# lampe.net
KiCad netlist of a schematic drawn in EAGLE
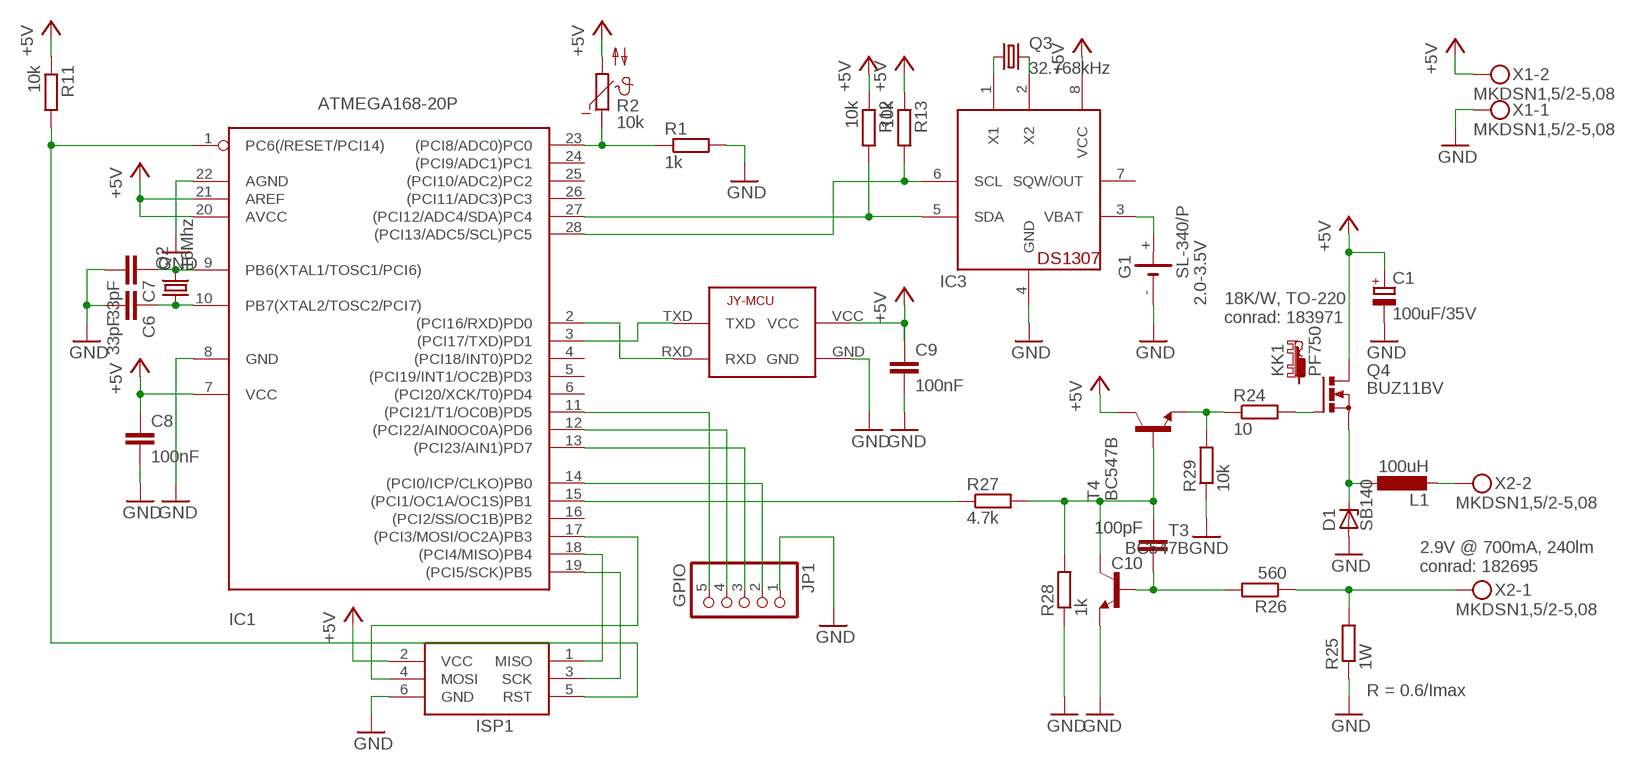
[diagram p0: schematic, sheet 1]

(export (version "E")
  (design (tool "Eeschema 10.0.6"))
  (components
    (comp (ref "C1")
      (value "100uF/35V")
      (footprint "eagle-import:E5-6")
      (libsource (lib "eagle-import") (part "CPOL-EUE5-6"))
    )
    (comp (ref "C6")
      (value "33pF")
      (footprint "eagle-import:C050-025X075")
      (libsource (lib "eagle-import") (part "C-EU050-025X075"))
    )
    (comp (ref "C7")
      (value "33pF")
      (footprint "eagle-import:C025-025X050")
      (libsource (lib "eagle-import") (part "C-EU025-025X050"))
    )
    (comp (ref "C8")
      (value "100nF")
      (footprint "eagle-import:C025-025X050")
      (libsource (lib "eagle-import") (part "C-EU025-025X050"))
    )
    (comp (ref "C9")
      (value "100nF")
      (footprint "eagle-import:C025-025X050")
      (libsource (lib "eagle-import") (part "C-EU025-025X050"))
    )
    (comp (ref "C10")
      (value "100pF")
      (footprint "eagle-import:C025-025X050")
      (libsource (lib "eagle-import") (part "C-EU025-025X050"))
    )
    (comp (ref "D1")
      (value "SB140")
      (footprint "eagle-import:DO35Z10")
      (libsource (lib "eagle-import") (part "ZENER-DIODEDO35Z10"))
    )
    (comp (ref "G1")
      (value "SL-340/P")
      (footprint "eagle-import:BEL_P")
      (libsource (lib "eagle-import") (part "SL-340/P"))
    )
    (comp (ref "IC1")
      (value "ATMEGA168-20P")
      (footprint "eagle-import:DIL28-3")
      (libsource (lib "eagle-import") (part "ATMEGA168P-20"))
    )
    (comp (ref "IC3")
      (value "DS1307")
      (footprint "eagle-import:DIL08")
      (libsource (lib "eagle-import") (part "DS1307"))
    )
    (comp (ref "ISP1")
      (value "AVRISP-6")
      (footprint "eagle-import:AVRISP")
      (libsource (lib "eagle-import") (part "AVRISP-6"))
    )
    (comp (ref "JP1")
      (value "GPIO")
      (footprint "eagle-import:1X05")
      (libsource (lib "eagle-import") (part "PINHD-1X5"))
    )
    (comp (ref "KK1")
      (value "PF750")
      (footprint "eagle-import:PF752")
      (libsource (lib "eagle-import") (part "PF750"))
    )
    (comp (ref "L1")
      (value "100uH")
      (footprint "eagle-import:6000-XXXX-RC")
      (libsource (lib "eagle-import") (part "L-EU6000-XXX-RC"))
    )
    (comp (ref "Q2")
      (value "16Mhz")
      (footprint "eagle-import:HC18U-V")
      (libsource (lib "eagle-import") (part "CRYSTALHC18U-V"))
    )
    (comp (ref "Q3")
      (value "32.768kHz")
      (footprint "eagle-import:TC26V")
      (libsource (lib "eagle-import") (part "CRYSTALTC26V"))
    )
    (comp (ref "Q4")
      (value "BUZ11BV")
      (footprint "eagle-import:TO220BV")
      (libsource (lib "eagle-import") (part "BUZ11BV"))
    )
    (comp (ref "R1")
      (value "1k")
      (footprint "eagle-import:0204V")
      (libsource (lib "eagle-import") (part "R-EU_0204/2V"))
    )
    (comp (ref "R2")
      (value "10k")
      (footprint "eagle-import:B57164")
      (fields (field (name "MPN") "B57164K474K52"))
      (libsource (lib "eagle-import") (part "B57164"))
    )
    (comp (ref "R11")
      (value "10k")
      (footprint "eagle-import:0207_10")
      (libsource (lib "eagle-import") (part "R-EU_0207/10"))
    )
    (comp (ref "R12")
      (value "10k")
      (footprint "eagle-import:0204_5")
      (libsource (lib "eagle-import") (part "R-EU_0204/5"))
    )
    (comp (ref "R13")
      (value "10k")
      (footprint "eagle-import:0204V")
      (libsource (lib "eagle-import") (part "R-EU_0204/2V"))
    )
    (comp (ref "R24")
      (value "10")
      (footprint "eagle-import:0204_7")
      (libsource (lib "eagle-import") (part "R-EU_0204/7"))
    )
    (comp (ref "R25")
      (value "1W")
      (footprint "eagle-import:0411_12")
      (libsource (lib "eagle-import") (part "R-EU_0411/12"))
    )
    (comp (ref "R26")
      (value "560")
      (footprint "eagle-import:0207_17")
      (libsource (lib "eagle-import") (part "R-EU_0207/17"))
    )
    (comp (ref "R27")
      (value "4.7k")
      (footprint "eagle-import:0207_10")
      (libsource (lib "eagle-import") (part "R-EU_0207/10"))
    )
    (comp (ref "R28")
      (value "1k")
      (footprint "eagle-import:0204_5")
      (libsource (lib "eagle-import") (part "R-EU_0204/5"))
    )
    (comp (ref "R29")
      (value "10k")
      (footprint "eagle-import:0204V")
      (libsource (lib "eagle-import") (part "R-EU_0204/2V"))
    )
    (comp (ref "T3")
      (value "BC547B")
      (footprint "eagle-import:TO92-EBC")
      (libsource (lib "eagle-import") (part "-NPN-TO92-EBC"))
    )
    (comp (ref "T4")
      (value "BC547B")
      (footprint "eagle-import:TO92-EBC")
      (libsource (lib "eagle-import") (part "-NPN-TO92-EBC"))
    )
    (comp (ref "U$1")
      (value "JY-MCU")
      (footprint "eagle-import:JY-MCU")
      (libsource (lib "eagle-import") (part "JY-MCU"))
    )
    (comp (ref "X1")
      (value "MKDSN1,5/2-5,08")
      (footprint "eagle-import:MKDSN1,5_2-5,08")
      (libsource (lib "eagle-import") (part "MKDSN1,5/2-5,08"))
    )
    (comp (ref "X2")
      (value "MKDSN1,5/2-5,08")
      (footprint "eagle-import:MKDSN1,5_2-5,08")
      (libsource (lib "eagle-import") (part "MKDSN1,5/2-5,08"))
    )
  )
  (nets
    (net (code "1") (name "+5V") (class "Default")
      (node (ref "C1") (pin "+") (pinfunction "+_+") (pintype "passive"))
      (node (ref "C8") (pin "1") (pinfunction "1_1") (pintype "passive"))
      (node (ref "C9") (pin "1") (pinfunction "1_1") (pintype "passive"))
      (node (ref "IC1") (pin "20") (pinfunction "AVCC_20") (pintype "bidirectional"))
      (node (ref "IC1") (pin "21") (pinfunction "AREF_21") (pintype "bidirectional"))
      (node (ref "IC1") (pin "7") (pinfunction "VCC_7") (pintype "bidirectional"))
      (node (ref "IC3") (pin "8") (pinfunction "VCC_8") (pintype "power_in"))
      (node (ref "ISP1") (pin "2") (pinfunction "VCC_2") (pintype "power_in"))
      (node (ref "Q4") (pin "D") (pinfunction "D_D") (pintype "passive"))
      (node (ref "R11") (pin "1") (pinfunction "1_1") (pintype "passive"))
      (node (ref "R12") (pin "1") (pinfunction "1_1") (pintype "passive"))
      (node (ref "R13") (pin "1") (pinfunction "1_1") (pintype "passive"))
      (node (ref "R2") (pin "2") (pinfunction "2_2") (pintype "passive"))
      (node (ref "T4") (pin "C") (pinfunction "C_C") (pintype "passive"))
      (node (ref "U$1") (pin "VCC") (pinfunction "VCC_VCC") (pintype "bidirectional"))
      (node (ref "X1") (pin "2") (pinfunction "KL_2") (pintype "passive"))
    )
    (net (code "2") (name "GND") (class "Default")
      (node (ref "C1") (pin "-") (pinfunction "-_-") (pintype "passive"))
      (node (ref "C6") (pin "2") (pinfunction "2_2") (pintype "passive"))
      (node (ref "C7") (pin "2") (pinfunction "2_2") (pintype "passive"))
      (node (ref "C8") (pin "2") (pinfunction "2_2") (pintype "passive"))
      (node (ref "C9") (pin "2") (pinfunction "2_2") (pintype "passive"))
      (node (ref "D1") (pin "A") (pinfunction "A_A") (pintype "passive"))
      (node (ref "G1") (pin "-") (pinfunction "-_-") (pintype "passive"))
      (node (ref "IC1") (pin "22") (pinfunction "AGND_22") (pintype "bidirectional"))
      (node (ref "IC1") (pin "8") (pinfunction "GND_8") (pintype "bidirectional"))
      (node (ref "IC3") (pin "4") (pinfunction "GND_4") (pintype "power_in"))
      (node (ref "ISP1") (pin "6") (pinfunction "GND_6") (pintype "power_in"))
      (node (ref "JP1") (pin "1") (pinfunction "1_1") (pintype "passive"))
      (node (ref "R1") (pin "2") (pinfunction "2_2") (pintype "passive"))
      (node (ref "R25") (pin "1") (pinfunction "1_1") (pintype "passive"))
      (node (ref "R28") (pin "1") (pinfunction "1_1") (pintype "passive"))
      (node (ref "R29") (pin "1") (pinfunction "1_1") (pintype "passive"))
      (node (ref "T3") (pin "E") (pinfunction "E_E") (pintype "passive"))
      (node (ref "U$1") (pin "GND") (pinfunction "GND_GND") (pintype "bidirectional"))
      (node (ref "X1") (pin "1") (pinfunction "KL_1") (pintype "passive"))
    )
    (net (code "3") (name "Net-(C10-Pad1)") (class "Default")
      (node (ref "C10") (pin "1") (pinfunction "1_1") (pintype "passive"))
      (node (ref "R26") (pin "2") (pinfunction "2_2") (pintype "passive"))
      (node (ref "T3") (pin "B") (pinfunction "B_B") (pintype "passive"))
    )
    (net (code "4") (name "Net-(C10-Pad2)") (class "Default")
      (node (ref "C10") (pin "2") (pinfunction "2_2") (pintype "passive"))
      (node (ref "R27") (pin "2") (pinfunction "2_2") (pintype "passive"))
      (node (ref "R28") (pin "2") (pinfunction "2_2") (pintype "passive"))
      (node (ref "T3") (pin "C") (pinfunction "C_C") (pintype "passive"))
      (node (ref "T4") (pin "B") (pinfunction "B_B") (pintype "passive"))
    )
    (net (code "5") (name "Net-(D1-PadC)") (class "Default")
      (node (ref "D1") (pin "C") (pinfunction "C_C") (pintype "passive"))
      (node (ref "L1") (pin "1") (pinfunction "1_1") (pintype "passive"))
      (node (ref "Q4") (pin "S") (pinfunction "S_S") (pintype "passive"))
    )
    (net (code "6") (name "Net-(IC1-(PCI0{slash}ICP{slash}CLKO)PB0)") (class "Default")
      (node (ref "IC1") (pin "14") (pinfunction "(PCI0/ICP/CLKO)PB0_14") (pintype "bidirectional"))
      (node (ref "JP1") (pin "2") (pinfunction "2_2") (pintype "passive"))
    )
    (net (code "7") (name "Net-(IC1-(PCI1{slash}OC1A{slash}OC1S)PB1)") (class "Default")
      (node (ref "IC1") (pin "15") (pinfunction "(PCI1/OC1A/OC1S)PB1_15") (pintype "bidirectional"))
      (node (ref "R27") (pin "1") (pinfunction "1_1") (pintype "passive"))
    )
    (net (code "8") (name "Net-(IC1-(PCI3{slash}MOSI{slash}OC2A)PB3)") (class "Default")
      (node (ref "IC1") (pin "17") (pinfunction "(PCI3/MOSI/OC2A)PB3_17") (pintype "bidirectional"))
      (node (ref "ISP1") (pin "4") (pinfunction "MOSI_4") (pintype "output"))
    )
    (net (code "9") (name "Net-(IC1-(PCI4{slash}MISO)PB4)") (class "Default")
      (node (ref "IC1") (pin "18") (pinfunction "(PCI4/MISO)PB4_18") (pintype "bidirectional"))
      (node (ref "ISP1") (pin "1") (pinfunction "MISO_1") (pintype "input"))
    )
    (net (code "10") (name "Net-(IC1-(PCI5{slash}SCK)PB5)") (class "Default")
      (node (ref "IC1") (pin "19") (pinfunction "(PCI5/SCK)PB5_19") (pintype "bidirectional"))
      (node (ref "ISP1") (pin "3") (pinfunction "SCK_3") (pintype "output"))
    )
    (net (code "11") (name "Net-(IC1-(PCI8{slash}ADC0)PC0)") (class "Default")
      (node (ref "IC1") (pin "23") (pinfunction "(PCI8/ADC0)PC0_23") (pintype "bidirectional"))
      (node (ref "R1") (pin "1") (pinfunction "1_1") (pintype "passive"))
      (node (ref "R2") (pin "1") (pinfunction "1_1") (pintype "passive"))
    )
    (net (code "12") (name "Net-(IC1-(PCI12{slash}ADC4{slash}SDA)PC4)") (class "Default")
      (node (ref "IC1") (pin "27") (pinfunction "(PCI12/ADC4/SDA)PC4_27") (pintype "bidirectional"))
      (node (ref "IC3") (pin "5") (pinfunction "SDA_5") (pintype "bidirectional"))
      (node (ref "R12") (pin "2") (pinfunction "2_2") (pintype "passive"))
    )
    (net (code "13") (name "Net-(IC1-(PCI13{slash}ADC5{slash}SCL)PC5)") (class "Default")
      (node (ref "IC1") (pin "28") (pinfunction "(PCI13/ADC5/SCL)PC5_28") (pintype "bidirectional"))
      (node (ref "IC3") (pin "6") (pinfunction "SCL_6") (pintype "bidirectional"))
      (node (ref "R13") (pin "2") (pinfunction "2_2") (pintype "passive"))
    )
    (net (code "14") (name "Net-(IC1-(PCI16{slash}RXD)PD0)") (class "Default")
      (node (ref "IC1") (pin "2") (pinfunction "(PCI16/RXD)PD0_2") (pintype "bidirectional"))
      (node (ref "U$1") (pin "RXD") (pinfunction "RXD_RXD") (pintype "bidirectional"))
    )
    (net (code "15") (name "Net-(IC1-(PCI17{slash}TXD)PD1)") (class "Default")
      (node (ref "IC1") (pin "3") (pinfunction "(PCI17/TXD)PD1_3") (pintype "bidirectional"))
      (node (ref "U$1") (pin "TXD") (pinfunction "TXD_TXD") (pintype "bidirectional"))
    )
    (net (code "16") (name "Net-(IC1-(PCI21{slash}T1{slash}OC0B)PD5)") (class "Default")
      (node (ref "IC1") (pin "11") (pinfunction "(PCI21/T1/OC0B)PD5_11") (pintype "bidirectional"))
      (node (ref "JP1") (pin "5") (pinfunction "5_5") (pintype "passive"))
    )
    (net (code "17") (name "Net-(IC1-(PCI22{slash}AIN0OC0A)PD6)") (class "Default")
      (node (ref "IC1") (pin "12") (pinfunction "(PCI22/AIN0OC0A)PD6_12") (pintype "bidirectional"))
      (node (ref "JP1") (pin "4") (pinfunction "4_4") (pintype "passive"))
    )
    (net (code "18") (name "Net-(IC1-(PCI23{slash}AIN1)PD7)") (class "Default")
      (node (ref "IC1") (pin "13") (pinfunction "(PCI23/AIN1)PD7_13") (pintype "bidirectional"))
      (node (ref "JP1") (pin "3") (pinfunction "3_3") (pintype "passive"))
    )
    (net (code "19") (name "Net-(IC1-PB6(XTAL1{slash}TOSC1{slash}PCI6))") (class "Default")
      (node (ref "C7") (pin "1") (pinfunction "1_1") (pintype "passive"))
      (node (ref "IC1") (pin "9") (pinfunction "PB6(XTAL1/TOSC1/PCI6)_9") (pintype "bidirectional"))
      (node (ref "Q2") (pin "2") (pinfunction "2_2") (pintype "passive"))
    )
    (net (code "20") (name "Net-(IC1-PB7(XTAL2{slash}TOSC2{slash}PCI7))") (class "Default")
      (node (ref "C6") (pin "1") (pinfunction "1_1") (pintype "passive"))
      (node (ref "IC1") (pin "10") (pinfunction "PB7(XTAL2/TOSC2/PCI7)_10") (pintype "bidirectional"))
      (node (ref "Q2") (pin "1") (pinfunction "1_1") (pintype "passive"))
    )
    (net (code "21") (name "Net-(IC1-PC6({slash}RESET{slash}PCI14))") (class "Default")
      (node (ref "IC1") (pin "1") (pinfunction "PC6(/RESET/PCI14)_1") (pintype "bidirectional"))
      (node (ref "ISP1") (pin "5") (pinfunction "RST_5") (pintype "output"))
      (node (ref "R11") (pin "2") (pinfunction "2_2") (pintype "passive"))
    )
    (net (code "22") (name "Net-(IC3-VBAT)") (class "Default")
      (node (ref "G1") (pin "+") (pinfunction "+_+") (pintype "passive"))
      (node (ref "IC3") (pin "3") (pinfunction "VBAT_3") (pintype "power_in"))
    )
    (net (code "23") (name "Net-(IC3-X1)") (class "Default")
      (node (ref "IC3") (pin "1") (pinfunction "X1_1") (pintype "passive"))
      (node (ref "Q3") (pin "1") (pinfunction "1_1") (pintype "passive"))
    )
    (net (code "24") (name "Net-(IC3-X2)") (class "Default")
      (node (ref "IC3") (pin "2") (pinfunction "X2_2") (pintype "passive"))
      (node (ref "Q3") (pin "2") (pinfunction "2_2") (pintype "passive"))
    )
    (net (code "25") (name "Net-(Q4-PadG)") (class "Default")
      (node (ref "Q4") (pin "G") (pinfunction "G_G") (pintype "passive"))
      (node (ref "R24") (pin "2") (pinfunction "2_2") (pintype "passive"))
    )
    (net (code "26") (name "Net-(R24-Pad1)") (class "Default")
      (node (ref "R24") (pin "1") (pinfunction "1_1") (pintype "passive"))
      (node (ref "R29") (pin "2") (pinfunction "2_2") (pintype "passive"))
      (node (ref "T4") (pin "E") (pinfunction "E_E") (pintype "passive"))
    )
    (net (code "27") (name "Net-(X2A-KL)") (class "Default")
      (node (ref "R25") (pin "2") (pinfunction "2_2") (pintype "passive"))
      (node (ref "R26") (pin "1") (pinfunction "1_1") (pintype "passive"))
      (node (ref "X2") (pin "1") (pinfunction "KL_1") (pintype "passive"))
    )
    (net (code "28") (name "Net-(X2B-KL)") (class "Default")
      (node (ref "L1") (pin "2") (pinfunction "2_2") (pintype "passive"))
      (node (ref "X2") (pin "2") (pinfunction "KL_2") (pintype "passive"))
    )
    (net (code "29") (name "unconnected-(IC1-(PCI2{slash}SS{slash}OC1B)PB2-Pad16)") (class "Default")
      (node (ref "IC1") (pin "16") (pinfunction "(PCI2/SS/OC1B)PB2_16") (pintype "bidirectional"))
    )
    (net (code "30") (name "unconnected-(IC1-(PCI9{slash}ADC1)PC1-Pad24)") (class "Default")
      (node (ref "IC1") (pin "24") (pinfunction "(PCI9/ADC1)PC1_24") (pintype "bidirectional"))
    )
    (net (code "31") (name "unconnected-(IC1-(PCI10{slash}ADC2)PC2-Pad25)") (class "Default")
      (node (ref "IC1") (pin "25") (pinfunction "(PCI10/ADC2)PC2_25") (pintype "bidirectional"))
    )
    (net (code "32") (name "unconnected-(IC1-(PCI11{slash}ADC3)PC3-Pad26)") (class "Default")
      (node (ref "IC1") (pin "26") (pinfunction "(PCI11/ADC3)PC3_26") (pintype "bidirectional"))
    )
    (net (code "33") (name "unconnected-(IC1-(PCI18{slash}INT0)PD2-Pad4)") (class "Default")
      (node (ref "IC1") (pin "4") (pinfunction "(PCI18/INT0)PD2_4") (pintype "bidirectional"))
    )
    (net (code "34") (name "unconnected-(IC1-(PCI19{slash}INT1{slash}OC2B)PD3-Pad5)") (class "Default")
      (node (ref "IC1") (pin "5") (pinfunction "(PCI19/INT1/OC2B)PD3_5") (pintype "bidirectional"))
    )
    (net (code "35") (name "unconnected-(IC1-(PCI20{slash}XCK{slash}T0)PD4-Pad6)") (class "Default")
      (node (ref "IC1") (pin "6") (pinfunction "(PCI20/XCK/T0)PD4_6") (pintype "bidirectional"))
    )
    (net (code "36") (name "unconnected-(IC3-SQW{slash}OUT-Pad7)") (class "Default")
      (node (ref "IC3") (pin "7") (pinfunction "SQW/OUT_7") (pintype "bidirectional"))
    )
  )
)
